# Schematic.net
KiCad netlist of a schematic drawn in Altium Designer
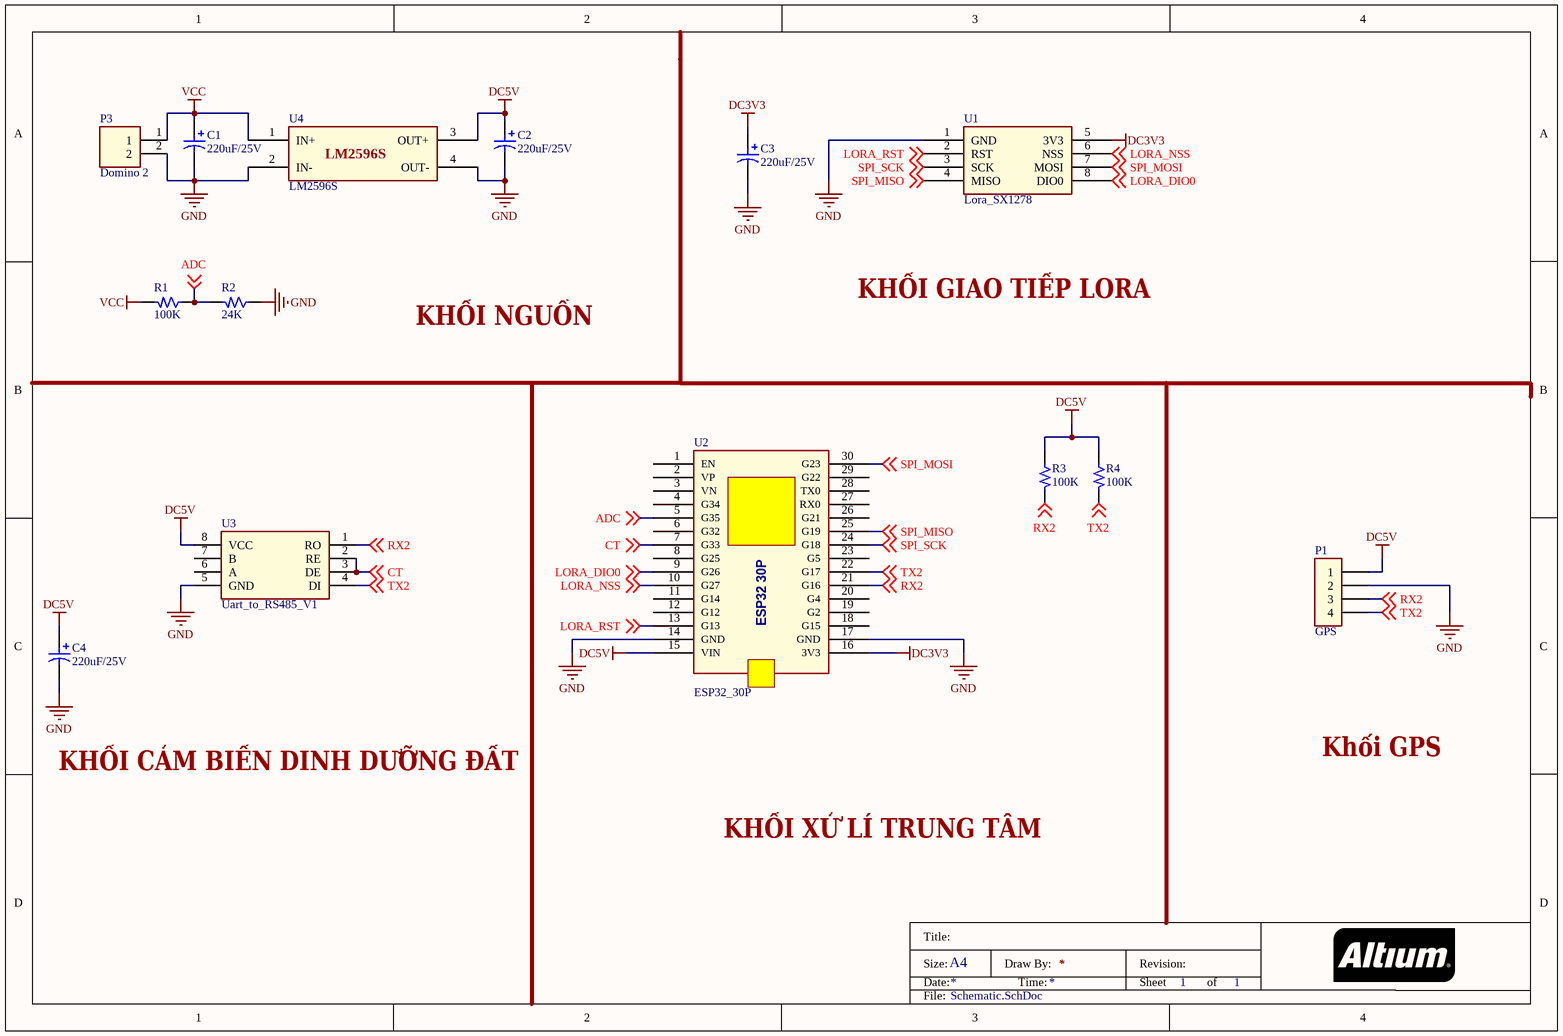
[diagram p0: Schematic.SchDoc]

(export (version "E")
  (design (tool "Eeschema 10.0.6"))
  (components
    (comp (ref "C1")
      (value "220uF/25V")
      (footprint "CAP-ALUM-10x12.5")
      (description "Capacitor Aluminum 220uF 20% 25V Radial")
      (fields (field (name "MPN") "CLA4514"))
      (libsource (lib "SachTranLib") (part "EEUTA1E221"))
    )
    (comp (ref "C2")
      (value "220uF/25V")
      (footprint "CAP-ALUM-10x12.5")
      (description "Capacitor Aluminum 220uF 20% 25V Radial")
      (fields (field (name "MPN") "CLA4514"))
      (libsource (lib "SachTranLib") (part "EEUTA1E221"))
    )
    (comp (ref "C3")
      (value "220uF/25V")
      (footprint "CAP-ALUM-10x12.5")
      (description "Capacitor Aluminum 220uF 20% 25V Radial")
      (fields (field (name "MPN") "CLA4514"))
      (libsource (lib "SachTranLib") (part "EEUTA1E221"))
    )
    (comp (ref "C4")
      (value "220uF/25V")
      (footprint "CAP-ALUM-10x12.5")
      (description "Capacitor Aluminum 220uF 20% 25V Radial")
      (fields (field (name "MPN") "CLA4514"))
      (libsource (lib "SachTranLib") (part "EEUTA1E221"))
    )
    (comp (ref "P1")
      (value "GPS")
      (footprint "B4B-XH-A")
      (description "Connector Header Through Hole 4 position 0.098\" (2.50mm)")
      (libsource (lib "SachTranLib") (part "B4B-XH-A"))
    )
    (comp (ref "P3")
      (value "Domino 2")
      (footprint "Domino-2")
      (libsource (lib "SachTranLib") (part "Domino-2"))
    )
    (comp (ref "R1")
      (value "100K")
      (footprint "R1/4W-H1")
      (description "Resistor 1/4W Through Hole")
      (libsource (lib "SachTranLib") (part "RES-1/4W"))
    )
    (comp (ref "R2")
      (value "24K")
      (footprint "R1/4W-H1")
      (description "Resistor 1/4W Through Hole")
      (libsource (lib "SachTranLib") (part "RES-1/4W"))
    )
    (comp (ref "R3")
      (value "100K")
      (footprint "R1/4W-H1")
      (description "Resistor 1/4W Through Hole")
      (libsource (lib "SachTranLib") (part "RES-1/4W"))
    )
    (comp (ref "R4")
      (value "100K")
      (footprint "R1/4W-H1")
      (description "Resistor 1/4W Through Hole")
      (libsource (lib "SachTranLib") (part "RES-1/4W"))
    )
    (comp (ref "U1")
      (value "Lora_SX1278")
      (footprint "Module-LORA-SX1278")
      (description "Module Lora SX1278 RA02 SPI")
      (libsource (lib "SachTranLib") (part "Module-Lora-SX1278-SPI"))
    )
    (comp (ref "U2")
      (value "ESP32_30P")
      (footprint "Kit-ESP32-30P")
      (description "Kit ESP32 30P")
      (libsource (lib "SachTranLib") (part "Kit_ESP32_30P"))
    )
    (comp (ref "U3")
      (value "Uart_to_RS485_V1")
      (footprint "Module-Uart-RS485-V1")
      (description "Module Uart to RS485 V1")
      (libsource (lib "SachTranLib") (part "Module-Uart-to-RS485-V1"))
    )
    (comp (ref "U4")
      (value "LM2596S")
      (footprint "Module-LM2596S")
      (description "Module LM2596S")
      (libsource (lib "SachTranLib") (part "Module-LM2596S"))
    )
  )
  (nets
    (net (code "1") (name "ADC") (class "Default")
      (node (ref "R1") (pin "1") (pinfunction "1_1") (pintype "passive"))
      (node (ref "R2") (pin "2") (pinfunction "2_2") (pintype "passive"))
      (node (ref "U2") (pin "5") (pinfunction "G35_5") (pintype "passive"))
    )
    (net (code "2") (name "CT") (class "Default")
      (node (ref "U2") (pin "7") (pinfunction "G33_7") (pintype "passive"))
      (node (ref "U3") (pin "2") (pinfunction "RE_2") (pintype "passive"))
      (node (ref "U3") (pin "3") (pinfunction "DE_3") (pintype "passive"))
    )
    (net (code "3") (name "DC3V3") (class "Default")
      (node (ref "C3") (pin "1") (pinfunction "1_1") (pintype "passive"))
      (node (ref "U1") (pin "5") (pinfunction "3V3_5") (pintype "passive"))
      (node (ref "U2") (pin "16") (pinfunction "3V3_16") (pintype "passive"))
    )
    (net (code "4") (name "DC5V") (class "Default")
      (node (ref "C2") (pin "1") (pinfunction "1_1") (pintype "passive"))
      (node (ref "C4") (pin "1") (pinfunction "1_1") (pintype "passive"))
      (node (ref "P1") (pin "1") (pinfunction "1_1") (pintype "passive"))
      (node (ref "R3") (pin "1") (pinfunction "1_1") (pintype "passive"))
      (node (ref "R4") (pin "1") (pinfunction "1_1") (pintype "passive"))
      (node (ref "U2") (pin "15") (pinfunction "VIN_15") (pintype "passive"))
      (node (ref "U3") (pin "8") (pinfunction "VCC_8") (pintype "passive"))
      (node (ref "U4") (pin "3") (pinfunction "OUT+_3") (pintype "passive"))
    )
    (net (code "5") (name "GND") (class "Default")
      (node (ref "C1") (pin "2") (pinfunction "2_2") (pintype "passive"))
      (node (ref "C2") (pin "2") (pinfunction "2_2") (pintype "passive"))
      (node (ref "C3") (pin "2") (pinfunction "2_2") (pintype "passive"))
      (node (ref "C4") (pin "2") (pinfunction "2_2") (pintype "passive"))
      (node (ref "P1") (pin "2") (pinfunction "2_2") (pintype "passive"))
      (node (ref "P3") (pin "2") (pinfunction "_2_2") (pintype "passive"))
      (node (ref "R2") (pin "1") (pinfunction "1_1") (pintype "passive"))
      (node (ref "U1") (pin "1") (pinfunction "GND_1") (pintype "passive"))
      (node (ref "U2") (pin "14") (pinfunction "GND_14") (pintype "passive"))
      (node (ref "U2") (pin "17") (pinfunction "GND_17") (pintype "passive"))
      (node (ref "U3") (pin "5") (pinfunction "GND_5") (pintype "passive"))
      (node (ref "U4") (pin "2") (pinfunction "IN-_2") (pintype "passive"))
      (node (ref "U4") (pin "4") (pinfunction "OUT-_4") (pintype "passive"))
    )
    (net (code "6") (name "LORA_DIO0") (class "Default")
      (node (ref "U1") (pin "8") (pinfunction "DIO0_8") (pintype "passive"))
      (node (ref "U2") (pin "9") (pinfunction "G26_9") (pintype "passive"))
    )
    (net (code "7") (name "LORA_NSS") (class "Default")
      (node (ref "U1") (pin "6") (pinfunction "NSS_6") (pintype "passive"))
      (node (ref "U2") (pin "10") (pinfunction "G27_10") (pintype "passive"))
    )
    (net (code "8") (name "LORA_RST") (class "Default")
      (node (ref "U1") (pin "2") (pinfunction "RST_2") (pintype "passive"))
      (node (ref "U2") (pin "13") (pinfunction "G13_13") (pintype "passive"))
    )
    (net (code "9") (name "RX2") (class "Default")
      (node (ref "P1") (pin "3") (pinfunction "3_3") (pintype "passive"))
      (node (ref "R3") (pin "2") (pinfunction "2_2") (pintype "passive"))
      (node (ref "U2") (pin "21") (pinfunction "G16_21") (pintype "passive"))
      (node (ref "U3") (pin "1") (pinfunction "RO_1") (pintype "passive"))
    )
    (net (code "10") (name "SPI_MISO") (class "Default")
      (node (ref "U1") (pin "4") (pinfunction "MISO_4") (pintype "passive"))
      (node (ref "U2") (pin "25") (pinfunction "G19_25") (pintype "passive"))
    )
    (net (code "11") (name "SPI_MOSI") (class "Default")
      (node (ref "U1") (pin "7") (pinfunction "MOSI_7") (pintype "passive"))
      (node (ref "U2") (pin "30") (pinfunction "G23_30") (pintype "passive"))
    )
    (net (code "12") (name "SPI_SCK") (class "Default")
      (node (ref "U1") (pin "3") (pinfunction "SCK_3") (pintype "passive"))
      (node (ref "U2") (pin "24") (pinfunction "G18_24") (pintype "passive"))
    )
    (net (code "13") (name "TX2") (class "Default")
      (node (ref "P1") (pin "4") (pinfunction "4_4") (pintype "passive"))
      (node (ref "R4") (pin "2") (pinfunction "2_2") (pintype "passive"))
      (node (ref "U2") (pin "22") (pinfunction "G17_22") (pintype "passive"))
      (node (ref "U3") (pin "4") (pinfunction "DI_4") (pintype "passive"))
    )
    (net (code "14") (name "VCC") (class "Default")
      (node (ref "C1") (pin "1") (pinfunction "1_1") (pintype "passive"))
      (node (ref "P3") (pin "1") (pinfunction "1_1") (pintype "passive"))
      (node (ref "R1") (pin "2") (pinfunction "2_2") (pintype "passive"))
      (node (ref "U4") (pin "1") (pinfunction "IN+_1") (pintype "passive"))
    )
    (net (code "15") (name "unconnected-(U2-EN-Pad1)") (class "Default")
      (node (ref "U2") (pin "1") (pinfunction "EN_1") (pintype "passive"))
    )
    (net (code "16") (name "unconnected-(U2-G2-Pad19)") (class "Default")
      (node (ref "U2") (pin "19") (pinfunction "G2_19") (pintype "passive"))
    )
    (net (code "17") (name "unconnected-(U2-G4-Pad20)") (class "Default")
      (node (ref "U2") (pin "20") (pinfunction "G4_20") (pintype "passive"))
    )
    (net (code "18") (name "unconnected-(U2-G5-Pad23)") (class "Default")
      (node (ref "U2") (pin "23") (pinfunction "G5_23") (pintype "passive"))
    )
    (net (code "19") (name "unconnected-(U2-G12-Pad12)") (class "Default")
      (node (ref "U2") (pin "12") (pinfunction "G12_12") (pintype "passive"))
    )
    (net (code "20") (name "unconnected-(U2-G14-Pad11)") (class "Default")
      (node (ref "U2") (pin "11") (pinfunction "G14_11") (pintype "passive"))
    )
    (net (code "21") (name "unconnected-(U2-G15-Pad18)") (class "Default")
      (node (ref "U2") (pin "18") (pinfunction "G15_18") (pintype "passive"))
    )
    (net (code "22") (name "unconnected-(U2-G21-Pad26)") (class "Default")
      (node (ref "U2") (pin "26") (pinfunction "G21_26") (pintype "passive"))
    )
    (net (code "23") (name "unconnected-(U2-G22-Pad29)") (class "Default")
      (node (ref "U2") (pin "29") (pinfunction "G22_29") (pintype "passive"))
    )
    (net (code "24") (name "unconnected-(U2-G25-Pad8)") (class "Default")
      (node (ref "U2") (pin "8") (pinfunction "G25_8") (pintype "passive"))
    )
    (net (code "25") (name "unconnected-(U2-G32-Pad6)") (class "Default")
      (node (ref "U2") (pin "6") (pinfunction "G32_6") (pintype "passive"))
    )
    (net (code "26") (name "unconnected-(U2-G34-Pad4)") (class "Default")
      (node (ref "U2") (pin "4") (pinfunction "G34_4") (pintype "passive"))
    )
    (net (code "27") (name "unconnected-(U2-RX0-Pad27)") (class "Default")
      (node (ref "U2") (pin "27") (pinfunction "RX0_27") (pintype "passive"))
    )
    (net (code "28") (name "unconnected-(U2-TX0-Pad28)") (class "Default")
      (node (ref "U2") (pin "28") (pinfunction "TX0_28") (pintype "passive"))
    )
    (net (code "29") (name "unconnected-(U2-VN-Pad3)") (class "Default")
      (node (ref "U2") (pin "3") (pinfunction "VN_3") (pintype "passive"))
    )
    (net (code "30") (name "unconnected-(U2-VP-Pad2)") (class "Default")
      (node (ref "U2") (pin "2") (pinfunction "VP_2") (pintype "passive"))
    )
    (net (code "31") (name "unconnected-(U3-A-Pad6)") (class "Default")
      (node (ref "U3") (pin "6") (pinfunction "A_6") (pintype "passive"))
    )
    (net (code "32") (name "unconnected-(U3-B-Pad7)") (class "Default")
      (node (ref "U3") (pin "7") (pinfunction "B_7") (pintype "passive"))
    )
  )
)
